# RK3562-VCCIO2-VCCIO3.net
KiCad netlist of a schematic drawn in Altium Designer
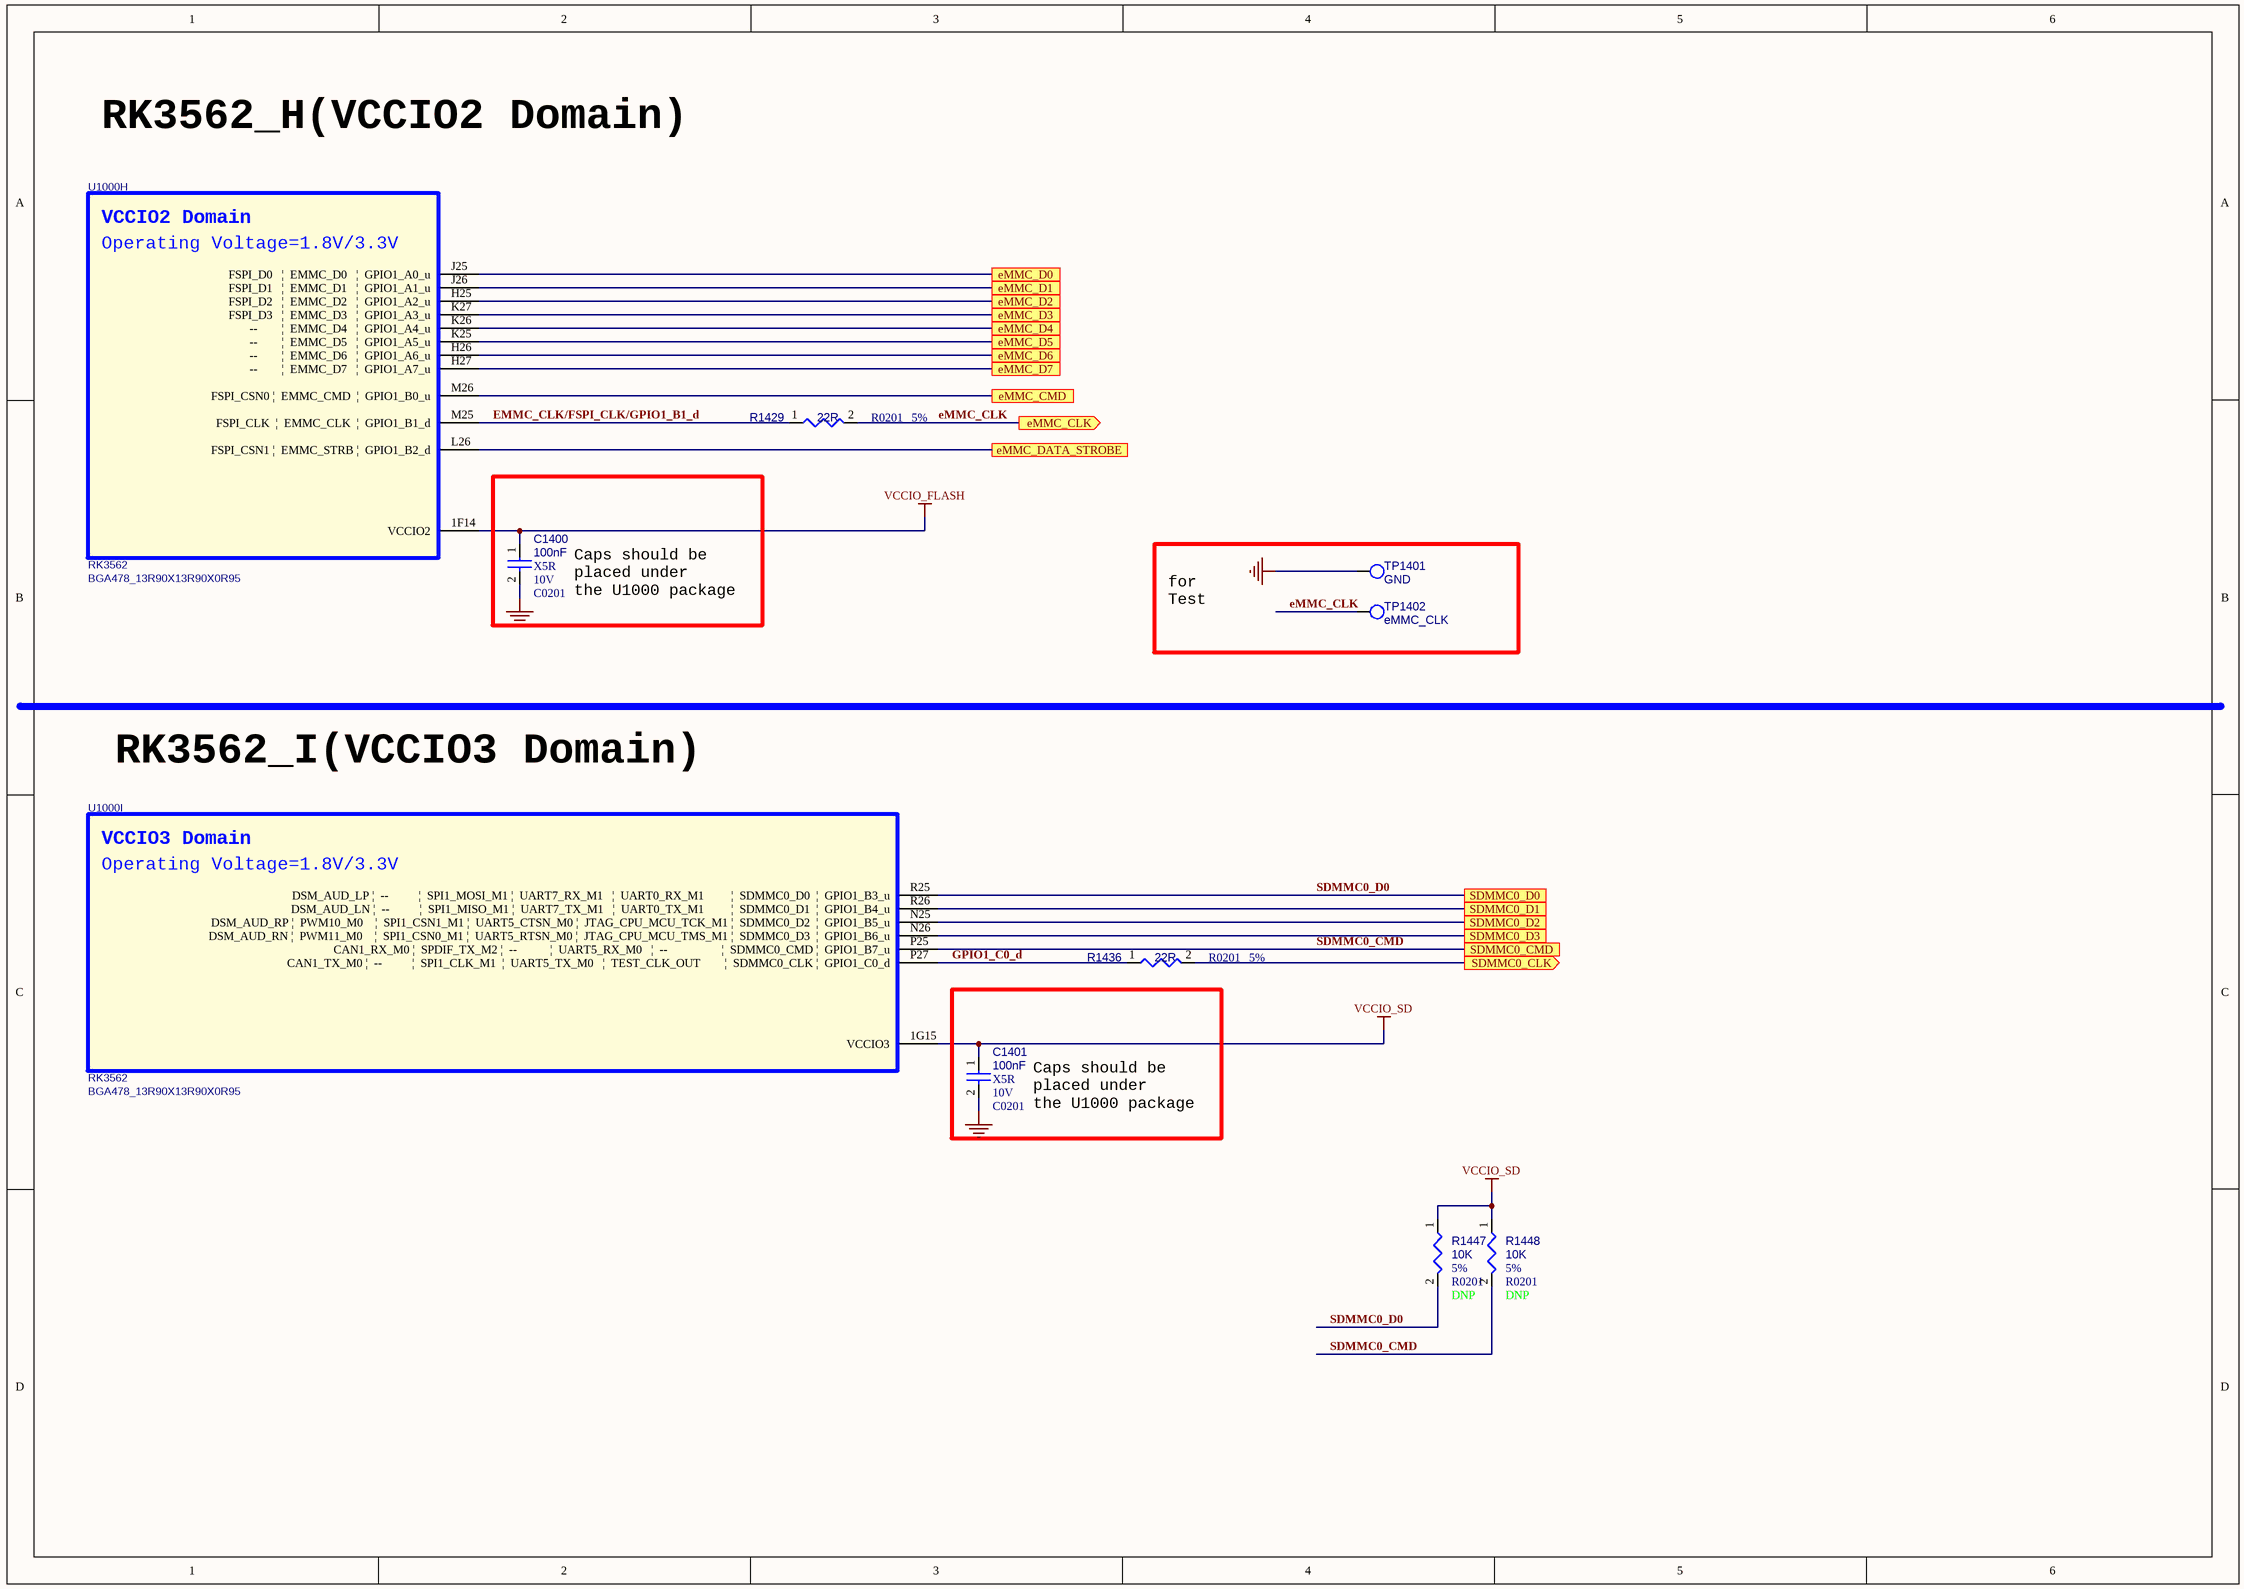
[diagram p0: RK3562-VCCIO2-VCCIO3.SchDoc]

(export (version "E")
  (design (tool "Eeschema 10.0.6"))
  (components
    (comp (ref "C1400")
      (value "100nF")
      (footprint "C0201")
      (description "cap,100.00nF,+/-10%,10V,X5R,C0201")
      (fields
        (field (name "DIELECTRIC") "X5R")
        (field (name "PCB FOOTPRINT") "C0201")
        (field (name "VOLTAGE") "10V")
        (field (name "MANUFACTURER") "TDK")
        (field (name "TOLERANCE") "10%")
        (field (name "CREATED BY") "JJJ")
      )
      (libsource (lib "RK3562_REF") (part "CAP NP"))
    )
    (comp (ref "C1401")
      (value "100nF")
      (footprint "C0201")
      (description "cap,100.00nF,+/-10%,10V,X5R,C0201")
      (fields
        (field (name "DIELECTRIC") "X5R")
        (field (name "PCB FOOTPRINT") "C0201")
        (field (name "VOLTAGE") "10V")
        (field (name "TOLERANCE") "10%")
        (field (name "MANUFACTURER") "TDK")
        (field (name "CREATED BY") "JJJ")
      )
      (libsource (lib "RK3562_REF") (part "CAP NP"))
    )
    (comp (ref "R1429")
      (value "22R")
      (footprint "R0201")
      (description "通用厚膜电阻,22R,+/-5%,R0201,1/20W.")
      (fields
        (field (name "TOLERANCE") "5%")
        (field (name "PCB FOOTPRINT") "R0201")
        (field (name "MANUFACTURER") "YAGEO")
        (field (name "CREATED BY") "YTL")
      )
      (libsource (lib "RK3562_REF") (part "RESISTOR"))
    )
    (comp (ref "R1436")
      (value "22R")
      (footprint "R0201")
      (description "通用厚膜电阻,22R,+/-5%,R0201,1/20W.")
      (fields
        (field (name "TOLERANCE") "5%")
        (field (name "PCB FOOTPRINT") "R0201")
        (field (name "MANUFACTURER") "YAGEO")
        (field (name "CREATED BY") "YTL")
      )
      (libsource (lib "RK3562_REF") (part "RESISTOR"))
    )
    (comp (ref "R1447")
      (value "10K")
      (footprint "R0201")
      (description "通用厚膜电阻,10K,+/-5%,R0201,1/20W.")
      (fields
        (field (name "TOLERANCE") "5%")
        (field (name "PCB FOOTPRINT") "R0201")
        (field (name "MANUFACTURER") "YAGEO")
        (field (name "OPTION") "DNP")
        (field (name "CREATED BY") "YTL")
      )
      (libsource (lib "RK3562_REF") (part "RESISTOR"))
    )
    (comp (ref "R1448")
      (value "10K")
      (footprint "R0201")
      (description "通用厚膜电阻,10K,+/-5%,R0201,1/20W.")
      (fields
        (field (name "TOLERANCE") "5%")
        (field (name "PCB FOOTPRINT") "R0201")
        (field (name "MANUFACTURER") "YAGEO")
        (field (name "OPTION") "DNP")
        (field (name "CREATED BY") "YTL")
      )
      (libsource (lib "RK3562_REF") (part "RESISTOR"))
    )
    (comp (ref "TP1401")
      (value "GND")
      (footprint "TP_0R70")
      (description "Test Point 0.7mm")
      (fields (field (name "CREATED BY") "JJJ"))
      (libsource (lib "RK3562_REF") (part "TP"))
    )
    (comp (ref "TP1402")
      (value "eMMC_CLK")
      (footprint "TP_0R70")
      (description "Test Point 0.7mm")
      (fields (field (name "CREATED BY") "JJJ"))
      (libsource (lib "RK3562_REF") (part "TP"))
    )
    (comp (ref "U1000")
      (value "RK3562")
      (footprint "BGA478_13R90X13R90X0R95")
      (description "ROCKCHIP SOC")
      (fields
        (field (name "PCB FOOTPRINT") "BGA478_13R90X13R90X0R95")
        (field (name "MANUFACTURER") "Rockchip (瑞芯微)")
        (field (name "CREATED BY") "JJJ")
      )
      (libsource (lib "RK3562_REF") (part "SOC_RK3562"))
    )
  )
  (nets
    (net (code "1") (name "/EMMC_CLK{slash}FSPI_CLK{slash}GPIO1_B1_d") (class "Default")
      (node (ref "R1429") (pin "1") (pinfunction "1_1") (pintype "passive"))
      (node (ref "U1000") (pin "M25") (pinfunction "FSPI_CLK__¦__EMMC_CLK__¦__GPIO1_B1_d_M25") (pintype "passive"))
    )
    (net (code "2") (name "/GPIO1_C0_d") (class "Default")
      (node (ref "R1436") (pin "1") (pinfunction "1_1") (pintype "passive"))
      (node (ref "U1000") (pin "P27") (pinfunction "CAN1_TX_M0_¦__--__________¦__SPI1_CLK_M1__¦__UART5_TX_M0___¦__TEST_CLK_OUT________¦__SDMMC0_CLK_¦__GPIO1_C0_d_P27") (pintype "passive"))
    )
    (net (code "3") (name "/SDMMC0_CLK") (class "Default")
      (node (ref "R1436") (pin "2") (pinfunction "2_2") (pintype "passive"))
    )
    (net (code "4") (name "/SDMMC0_CMD") (class "Default")
      (node (ref "R1448") (pin "2") (pinfunction "2_2") (pintype "passive"))
      (node (ref "U1000") (pin "P25") (pinfunction "CAN1_RX_M0_¦__SPDIF_TX_M2_¦__--___________¦__UART5_RX_M0___¦__--__________________¦__SDMMC0_CMD_¦__GPIO1_B7_u_P25") (pintype "passive"))
    )
    (net (code "5") (name "/SDMMC0_D0") (class "Default")
      (node (ref "R1447") (pin "2") (pinfunction "2_2") (pintype "passive"))
      (node (ref "U1000") (pin "R25") (pinfunction "DSM_AUD_LP_¦__--__________¦__SPI1_MOSI_M1_¦__UART7_RX_M1___¦__UART0_RX_M1_________¦__SDMMC0_D0__¦__GPIO1_B3_u_R25") (pintype "passive"))
    )
    (net (code "6") (name "/SDMMC0_D1") (class "Default")
      (node (ref "U1000") (pin "R26") (pinfunction "DSM_AUD_LN_¦__--__________¦__SPI1_MISO_M1_¦__UART7_TX_M1___¦__UART0_TX_M1_________¦__SDMMC0_D1__¦__GPIO1_B4_u_R26") (pintype "passive"))
    )
    (net (code "7") (name "/SDMMC0_D2") (class "Default")
      (node (ref "U1000") (pin "N25") (pinfunction "DSM_AUD_RP_¦__PWM10_M0____¦__SPI1_CSN1_M1_¦__UART5_CTSN_M0_¦__JTAG_CPU_MCU_TCK_M1_¦__SDMMC0_D2__¦__GPIO1_B5_u_N25") (pintype "passive"))
    )
    (net (code "8") (name "/SDMMC0_D3") (class "Default")
      (node (ref "U1000") (pin "N26") (pinfunction "DSM_AUD_RN_¦__PWM11_M0____¦__SPI1_CSN0_M1_¦__UART5_RTSN_M0_¦__JTAG_CPU_MCU_TMS_M1_¦__SDMMC0_D3__¦__GPIO1_B6_u_N26") (pintype "passive"))
    )
    (net (code "9") (name "/eMMC_CLK") (class "Default")
      (node (ref "R1429") (pin "2") (pinfunction "2_2") (pintype "passive"))
      (node (ref "TP1402") (pin "1") (pinfunction "1_1") (pintype "passive"))
    )
    (net (code "10") (name "/eMMC_CMD") (class "Default")
      (node (ref "U1000") (pin "M26") (pinfunction "FSPI_CSN0_¦__EMMC_CMD__¦__GPIO1_B0_u_M26") (pintype "passive"))
    )
    (net (code "11") (name "/eMMC_D0") (class "Default")
      (node (ref "U1000") (pin "J25") (pinfunction "FSPI_D0___¦__EMMC_D0___¦__GPIO1_A0_u_J25") (pintype "passive"))
    )
    (net (code "12") (name "/eMMC_D1") (class "Default")
      (node (ref "U1000") (pin "J26") (pinfunction "FSPI_D1___¦__EMMC_D1___¦__GPIO1_A1_u_J26") (pintype "passive"))
    )
    (net (code "13") (name "/eMMC_D2") (class "Default")
      (node (ref "U1000") (pin "H25") (pinfunction "FSPI_D2___¦__EMMC_D2___¦__GPIO1_A2_u_H25") (pintype "passive"))
    )
    (net (code "14") (name "/eMMC_D3") (class "Default")
      (node (ref "U1000") (pin "K27") (pinfunction "FSPI_D3___¦__EMMC_D3___¦__GPIO1_A3_u_K27") (pintype "passive"))
    )
    (net (code "15") (name "/eMMC_D4") (class "Default")
      (node (ref "U1000") (pin "K26") (pinfunction "--________¦__EMMC_D4___¦__GPIO1_A4_u_K26") (pintype "passive"))
    )
    (net (code "16") (name "/eMMC_D5") (class "Default")
      (node (ref "U1000") (pin "K25") (pinfunction "--________¦__EMMC_D5___¦__GPIO1_A5_u_K25") (pintype "passive"))
    )
    (net (code "17") (name "/eMMC_D6") (class "Default")
      (node (ref "U1000") (pin "H26") (pinfunction "--________¦__EMMC_D6___¦__GPIO1_A6_u_H26") (pintype "passive"))
    )
    (net (code "18") (name "/eMMC_D7") (class "Default")
      (node (ref "U1000") (pin "H27") (pinfunction "--________¦__EMMC_D7___¦__GPIO1_A7_u_H27") (pintype "passive"))
    )
    (net (code "19") (name "/eMMC_DATA_STROBE") (class "Default")
      (node (ref "U1000") (pin "L26") (pinfunction "FSPI_CSN1_¦__EMMC_STRB_¦__GPIO1_B2_d_L26") (pintype "passive"))
    )
    (net (code "20") (name "GND") (class "Default")
      (node (ref "C1400") (pin "2") (pinfunction "2_2") (pintype "passive"))
      (node (ref "C1401") (pin "2") (pinfunction "2_2") (pintype "passive"))
      (node (ref "TP1401") (pin "1") (pinfunction "1_1") (pintype "passive"))
    )
    (net (code "21") (name "VCCIO_FLASH") (class "Default")
      (node (ref "C1400") (pin "1") (pinfunction "1_1") (pintype "passive"))
      (node (ref "U1000") (pin "1F14") (pinfunction "VCCIO2_1F14") (pintype "passive"))
    )
    (net (code "22") (name "VCCIO_SD") (class "Default")
      (node (ref "C1401") (pin "1") (pinfunction "1_1") (pintype "passive"))
      (node (ref "R1447") (pin "1") (pinfunction "1_1") (pintype "passive"))
      (node (ref "R1448") (pin "1") (pinfunction "1_1") (pintype "passive"))
      (node (ref "U1000") (pin "1G15") (pinfunction "VCCIO3_1G15") (pintype "passive"))
    )
  )
)
